# Mechaduino01.net
KiCad netlist of a schematic drawn in EAGLE
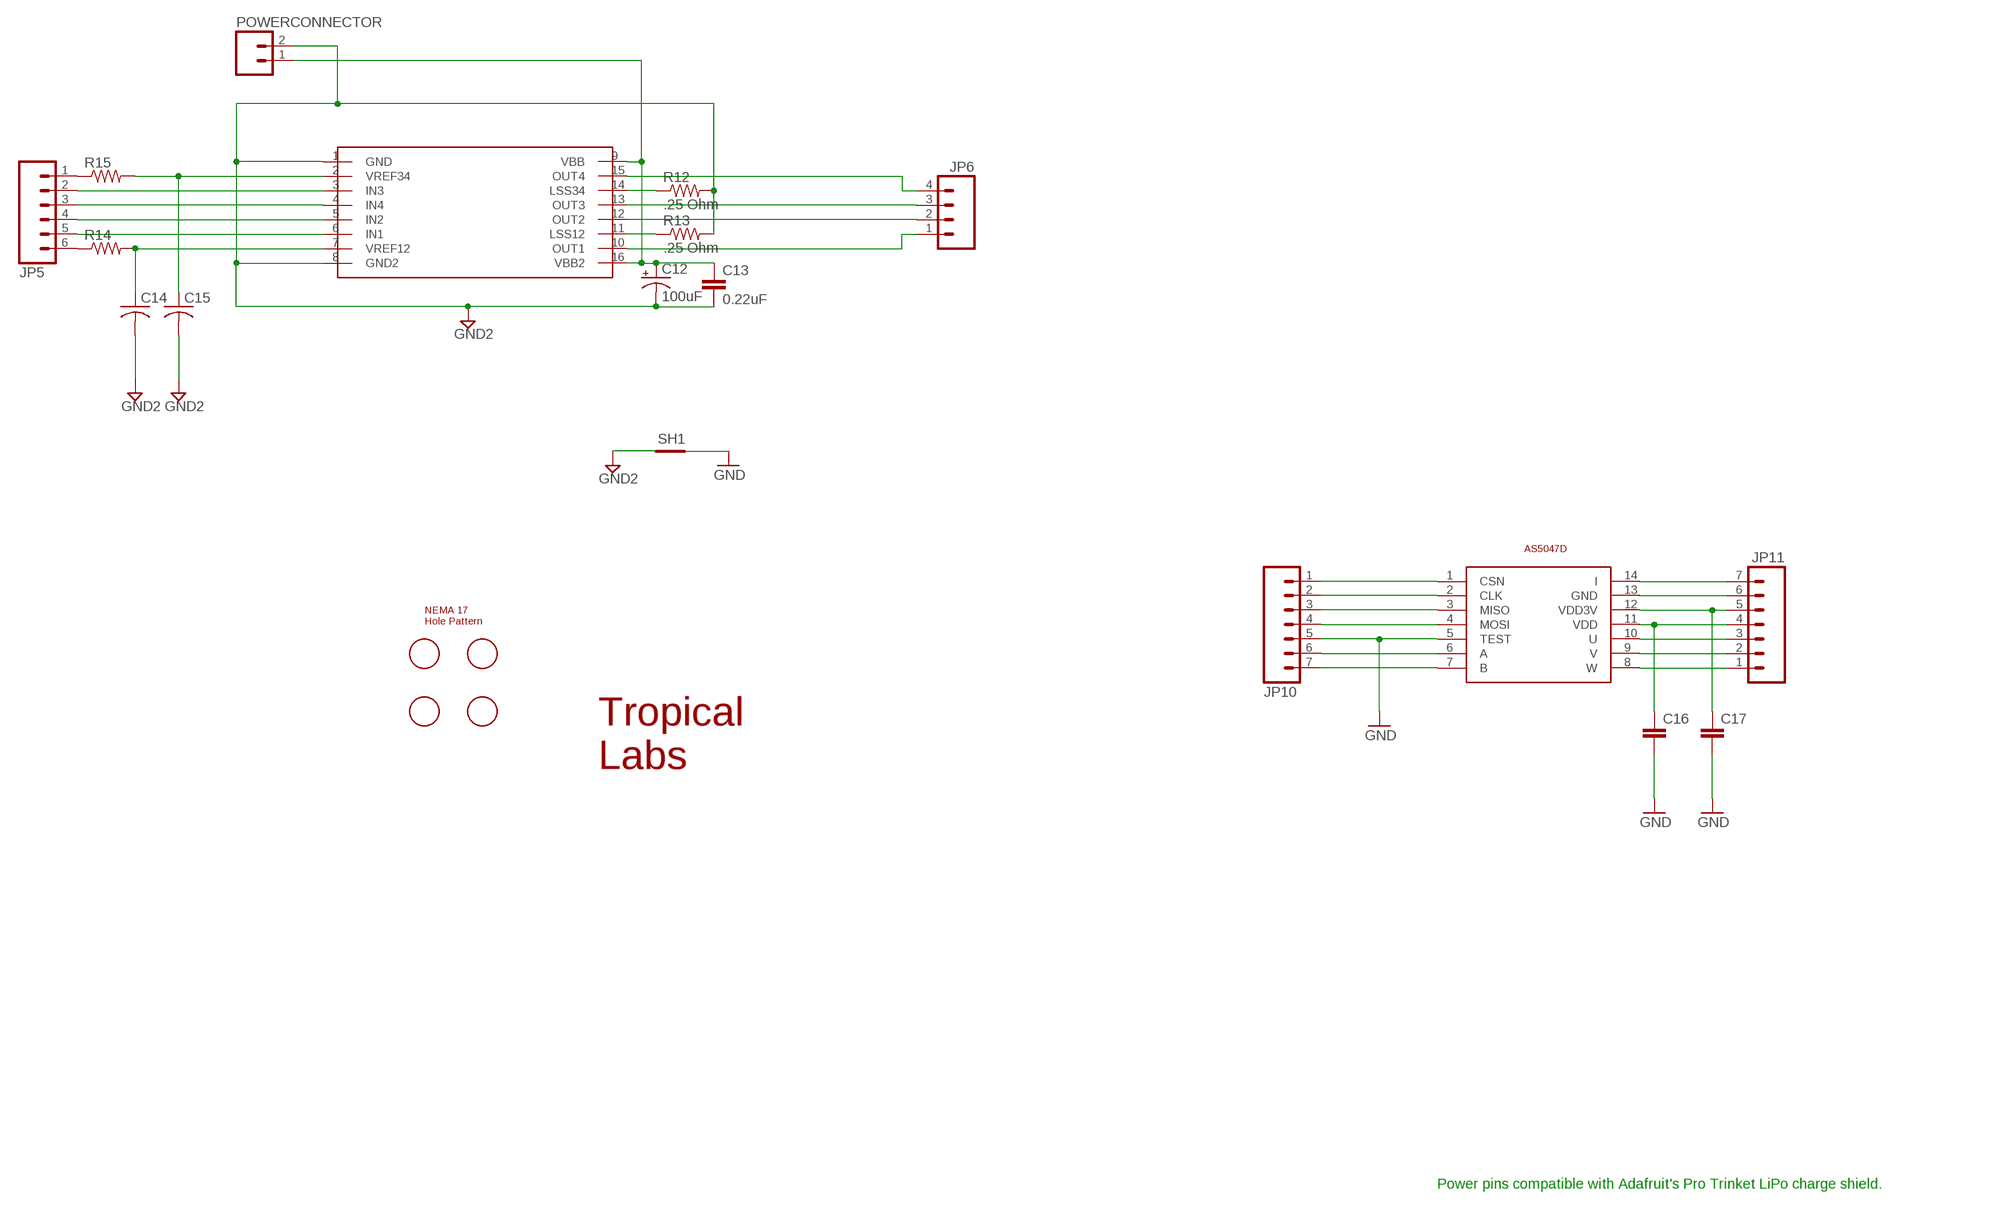
[diagram p0: schematic, sheet 1, part 1 of 2]
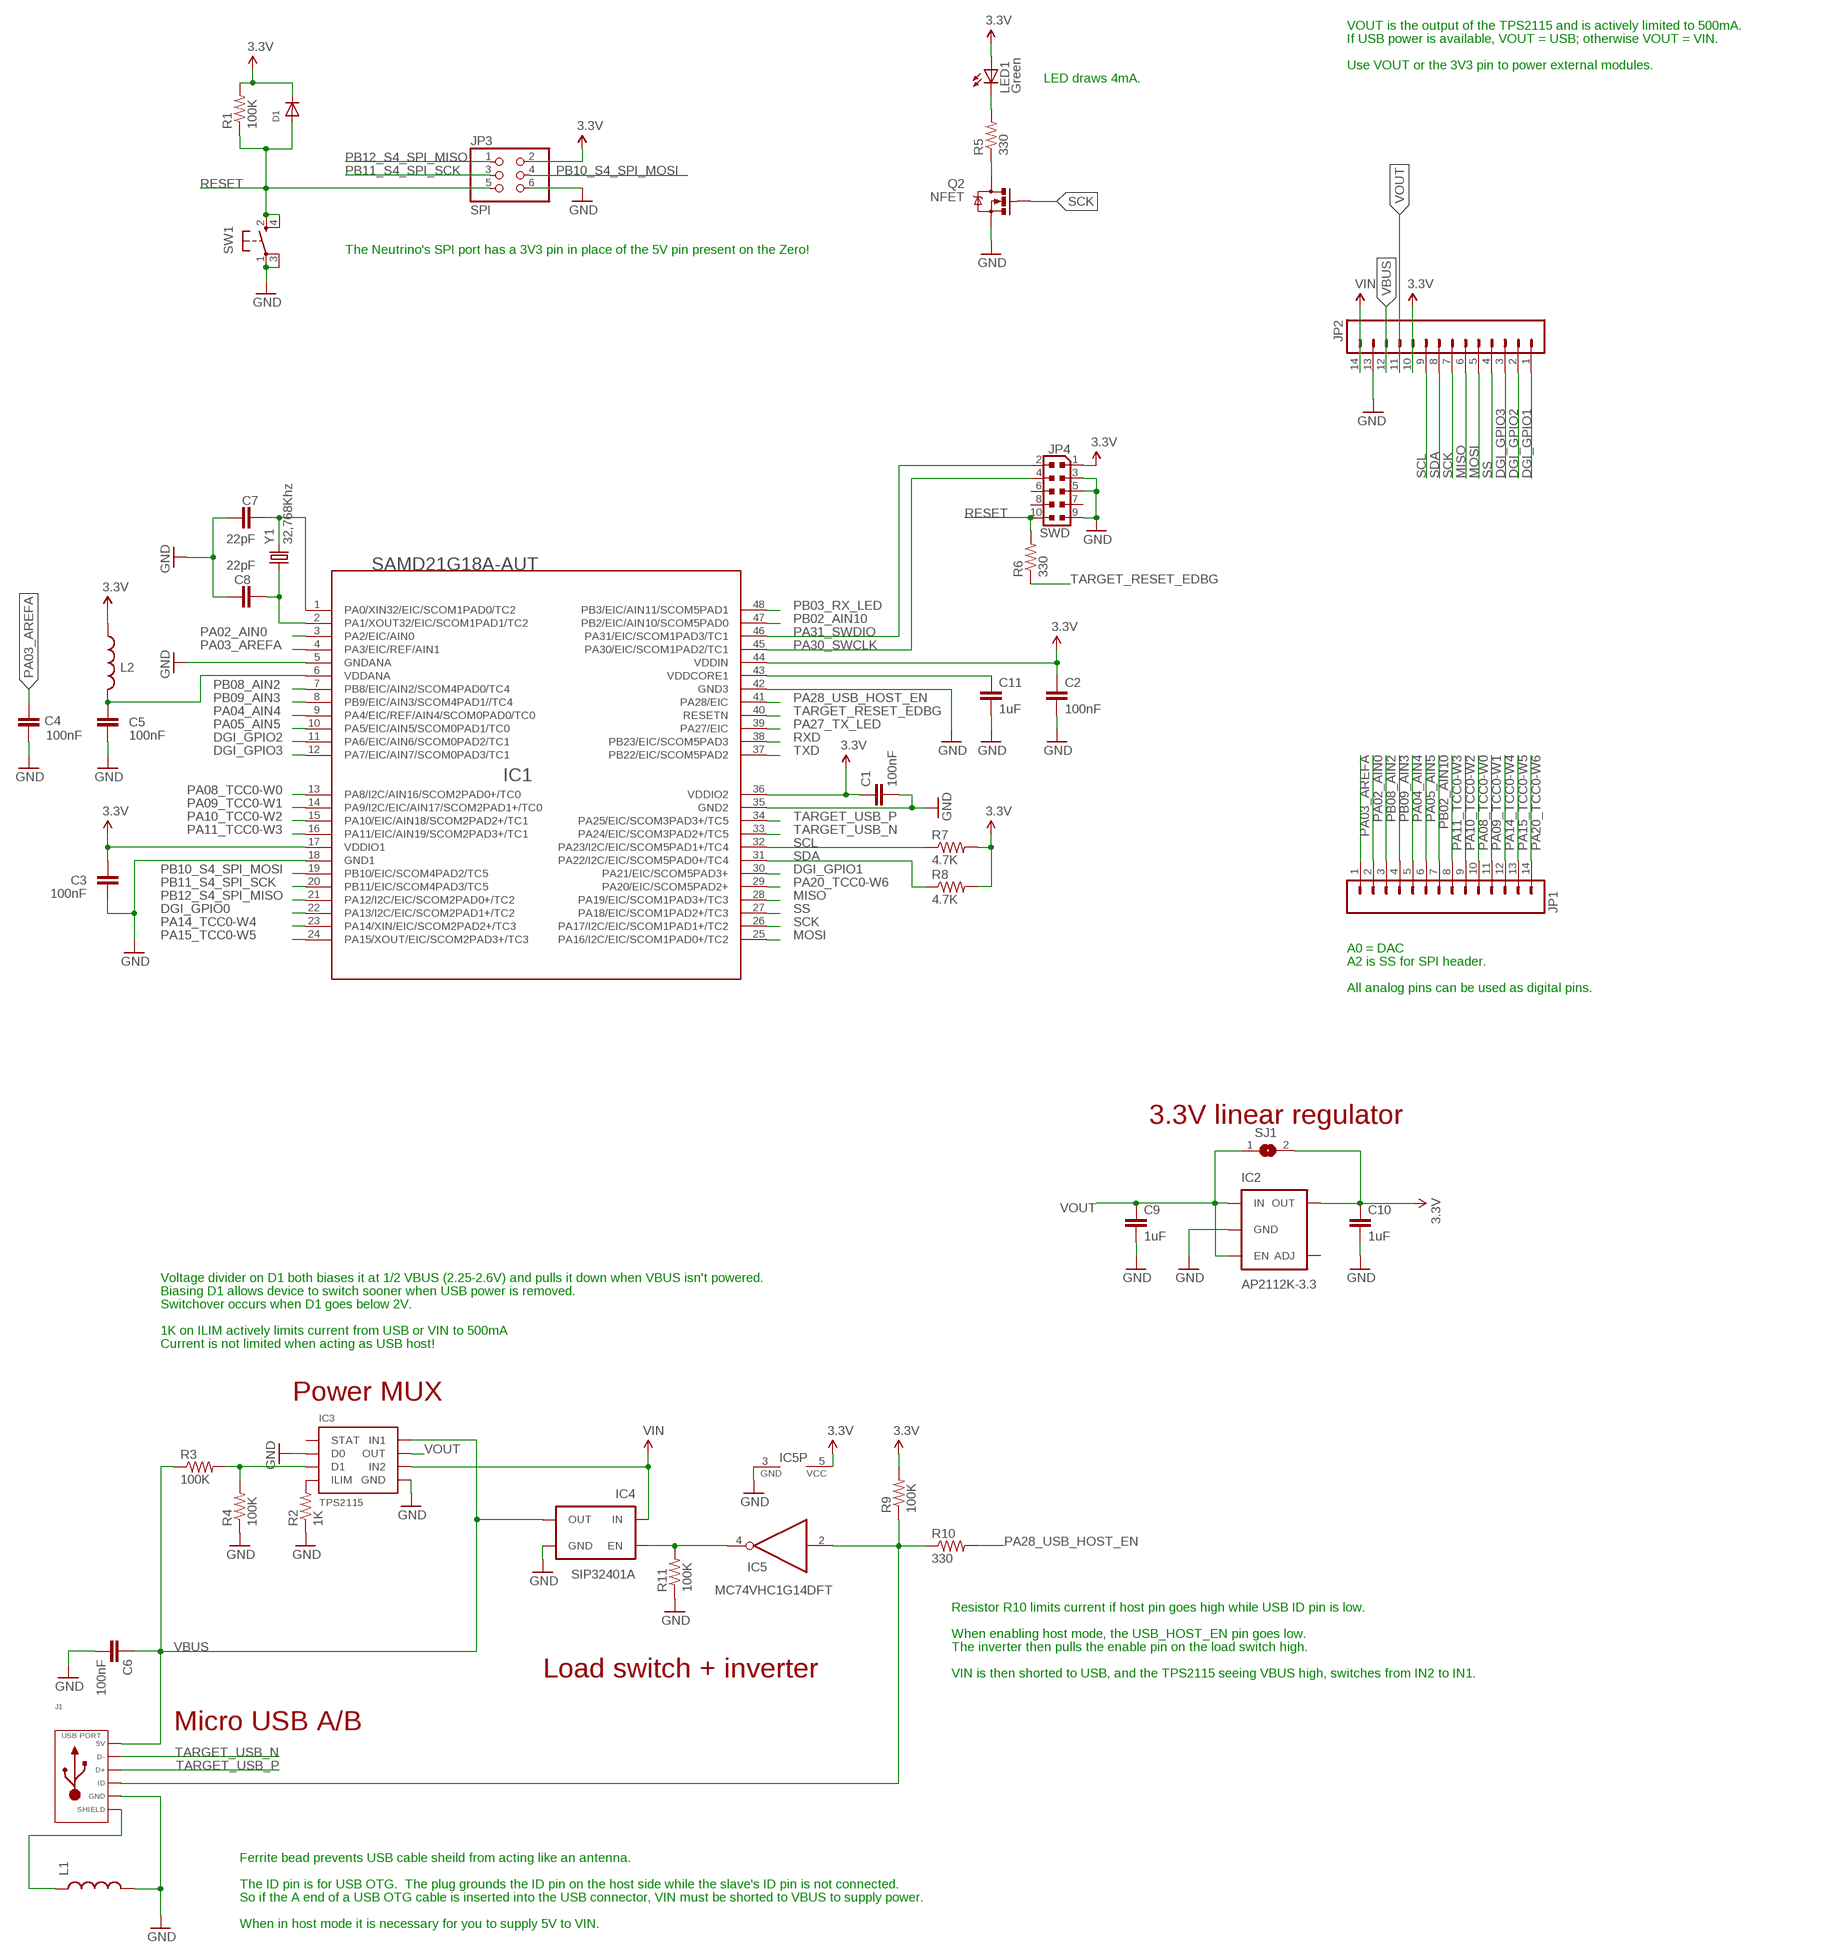
[diagram p1: schematic, sheet 1, part 2 of 2]

(export (version "E")
  (design (tool "Eeschema 10.0.6"))
  (components
    (comp (ref "C1")
      (value "100nF")
      (footprint "eagle-import:0402-CAP")
      (libsource (lib "eagle-import") (part "CAP0402"))
    )
    (comp (ref "C2")
      (value "100nF")
      (footprint "eagle-import:0402-CAP")
      (libsource (lib "eagle-import") (part "CAP0402"))
    )
    (comp (ref "C3")
      (value "100nF")
      (footprint "eagle-import:0402-CAP")
      (libsource (lib "eagle-import") (part "CAP0402"))
    )
    (comp (ref "C4")
      (value "100nF")
      (footprint "eagle-import:0402-CAP")
      (libsource (lib "eagle-import") (part "CAP0402"))
    )
    (comp (ref "C5")
      (value "100nF")
      (footprint "eagle-import:0402-CAP")
      (libsource (lib "eagle-import") (part "CAP0402"))
    )
    (comp (ref "C6")
      (value "100nF")
      (footprint "eagle-import:0402-CAP")
      (libsource (lib "eagle-import") (part "CAP0402"))
    )
    (comp (ref "C7")
      (value "22pF")
      (footprint "eagle-import:0402-CAP")
      (libsource (lib "eagle-import") (part "CAP0402"))
    )
    (comp (ref "C8")
      (value "22pF")
      (footprint "eagle-import:0402-CAP")
      (libsource (lib "eagle-import") (part "CAP0402"))
    )
    (comp (ref "C9")
      (value "1uF")
      (footprint "eagle-import:0402-CAP")
      (libsource (lib "eagle-import") (part "CAP0402"))
    )
    (comp (ref "C10")
      (value "1uF")
      (footprint "eagle-import:0402-CAP")
      (libsource (lib "eagle-import") (part "CAP0402"))
    )
    (comp (ref "C11")
      (value "1uF")
      (footprint "eagle-import:0402-CAP")
      (libsource (lib "eagle-import") (part "CAP0402"))
    )
    (comp (ref "C12")
      (value "100uF")
      (footprint "eagle-import:CPOL-RADIAL-100UF-25V")
      (libsource (lib "eagle-import") (part "CAP_POLPTH1"))
    )
    (comp (ref "C13")
      (value "0.22uF")
      (footprint "eagle-import:CAP-PTH-SMALLEZ")
      (libsource (lib "eagle-import") (part "CAPEZ"))
    )
    (comp (ref "C14")
      (value "C-US050-035X075")
      (footprint "eagle-import:C050-035X075")
      (libsource (lib "eagle-import") (part "C-US050-035X075"))
    )
    (comp (ref "C15")
      (value "C-US050-035X075")
      (footprint "eagle-import:C050-035X075")
      (libsource (lib "eagle-import") (part "C-US050-035X075"))
    )
    (comp (ref "C16")
      (value "CAP0402")
      (footprint "eagle-import:0402-CAP")
      (libsource (lib "eagle-import") (part "CAP0402"))
    )
    (comp (ref "C17")
      (value "CAP0402")
      (footprint "eagle-import:0402-CAP")
      (libsource (lib "eagle-import") (part "CAP0402"))
    )
    (comp (ref "D1")
      (value "DIODESOD-523")
      (footprint "eagle-import:SOD-523")
      (libsource (lib "eagle-import") (part "DIODESOD-523"))
    )
    (comp (ref "IC1")
      (value "SAMD21G18A-AUT")
      (footprint "eagle-import:INTEGRATEDCIRCUITS_TQFP48-7X7")
      (libsource (lib "eagle-import") (part "INTEGRATEDCIRCUITS_1792_SAMD21G18A-AUT"))
    )
    (comp (ref "IC2")
      (value "AP2112K-3.3")
      (footprint "eagle-import:SOT23-5")
      (libsource (lib "eagle-import") (part "AP2202-ADJ"))
    )
    (comp (ref "IC3")
      (value "TPS2115")
      (footprint "eagle-import:8-VDFN")
      (libsource (lib "eagle-import") (part "TPS2115"))
    )
    (comp (ref "IC4")
      (value "SIP32401A")
      (footprint "eagle-import:TDFN4")
      (libsource (lib "eagle-import") (part "SIP32401A"))
    )
    (comp (ref "IC5")
      (value "MC74VHC1G14DFT")
      (footprint "eagle-import:SC70-5")
      (libsource (lib "eagle-import") (part "741G04DCKAHC"))
    )
    (comp (ref "J1")
      (value "USB_MICRO_RIGHT")
      (footprint "eagle-import:MICROUSB-RIGHT")
      (libsource (lib "eagle-import") (part "USB_MICRO_RIGHT"))
    )
    (comp (ref "JP1")
      (value "M14NOSILK_SMALLPADS")
      (footprint "eagle-import:1X14_NO_SILK_SMALLPADS")
      (libsource (lib "eagle-import") (part "M14NOSILK_SMALLPADS"))
    )
    (comp (ref "JP2")
      (value "M14NOSILK_SMALLPADS")
      (footprint "eagle-import:1X14_NO_SILK_SMALLPADS")
      (libsource (lib "eagle-import") (part "M14NOSILK_SMALLPADS"))
    )
    (comp (ref "JP3")
      (value "SPI")
      (footprint "eagle-import:CONNETTORI_2X03")
      (fields (field (name "PART_NUMBER") "PH254-203DF118A00V"))
      (libsource (lib "eagle-import") (part "CONNETTORI_0114_PH254-203DF118A00V"))
    )
    (comp (ref "JP4")
      (value "SWD")
      (footprint "eagle-import:CONNETTORI_PINHEAD-2X5-P127")
      (libsource (lib "eagle-import") (part "CONNETTORI_0171_PH127-205DF055G00A"))
    )
    (comp (ref "JP5")
      (value "M06SILK_FEMALE_PTH")
      (footprint "eagle-import:1X06")
      (libsource (lib "eagle-import") (part "M06SILK_FEMALE_PTH"))
    )
    (comp (ref "JP6")
      (value "M04PTH")
      (footprint "eagle-import:1X04")
      (libsource (lib "eagle-import") (part "M04PTH"))
    )
    (comp (ref "JP10")
      (value "M07")
      (footprint "eagle-import:1X07")
      (libsource (lib "eagle-import") (part "M07"))
    )
    (comp (ref "JP11")
      (value "M07")
      (footprint "eagle-import:1X07")
      (libsource (lib "eagle-import") (part "M07"))
    )
    (comp (ref "L1")
      (value "INDUCTOR0603-TDK")
      (footprint "eagle-import:0603-TDK")
      (libsource (lib "eagle-import") (part "INDUCTOR0603-TDK"))
    )
    (comp (ref "L2")
      (value "INDUCTOR0603-TDK")
      (footprint "eagle-import:0603-TDK")
      (libsource (lib "eagle-import") (part "INDUCTOR0603-TDK"))
    )
    (comp (ref "LED1")
      (value "Green")
      (footprint "eagle-import:CHIPLED_0805")
      (fields (field (name "PART_NUMBER") "KPT-2012YC"))
      (libsource (lib "eagle-import") (part "0044_KPT-2012YC"))
    )
    (comp (ref "POWERCONNECTOR")
      (value "M025MM")
      (footprint "eagle-import:SCREWTERMINAL-5MM-2")
      (libsource (lib "eagle-import") (part "M025MM"))
    )
    (comp (ref "Q2")
      (value "NFET")
      (footprint "eagle-import:SOT323")
      (libsource (lib "eagle-import") (part "MOSFET-NCHANNEL2N7002PW"))
    )
    (comp (ref "R1")
      (value "100K")
      (footprint "eagle-import:R0402-VISHAY")
      (libsource (lib "eagle-import") (part "R-US_R0402-VISHAY"))
    )
    (comp (ref "R2")
      (value "1K")
      (footprint "eagle-import:R0402-VISHAY")
      (libsource (lib "eagle-import") (part "R-US_R0402-VISHAY"))
    )
    (comp (ref "R3")
      (value "100K")
      (footprint "eagle-import:R0402-VISHAY")
      (libsource (lib "eagle-import") (part "R-US_R0402-VISHAY"))
    )
    (comp (ref "R4")
      (value "100K")
      (footprint "eagle-import:R0402-VISHAY")
      (libsource (lib "eagle-import") (part "R-US_R0402-VISHAY"))
    )
    (comp (ref "R5")
      (value "330")
      (footprint "eagle-import:R0402-VISHAY")
      (libsource (lib "eagle-import") (part "R-US_R0402-VISHAY"))
    )
    (comp (ref "R6")
      (value "330")
      (footprint "eagle-import:R0402-VISHAY")
      (libsource (lib "eagle-import") (part "R-US_R0402-VISHAY"))
    )
    (comp (ref "R7")
      (value "4.7K")
      (footprint "eagle-import:R0402-VISHAY")
      (libsource (lib "eagle-import") (part "R-US_R0402-VISHAY"))
    )
    (comp (ref "R8")
      (value "4.7K")
      (footprint "eagle-import:R0402-VISHAY")
      (libsource (lib "eagle-import") (part "R-US_R0402-VISHAY"))
    )
    (comp (ref "R9")
      (value "100K")
      (footprint "eagle-import:R0402-VISHAY")
      (libsource (lib "eagle-import") (part "R-US_R0402-VISHAY"))
    )
    (comp (ref "R10")
      (value "330")
      (footprint "eagle-import:R0402-VISHAY")
      (libsource (lib "eagle-import") (part "R-US_R0402-VISHAY"))
    )
    (comp (ref "R11")
      (value "100K")
      (footprint "eagle-import:R0402-VISHAY")
      (libsource (lib "eagle-import") (part "R-US_R0402-VISHAY"))
    )
    (comp (ref "R12")
      (value ".25 Ohm")
      (footprint "eagle-import:0204V")
      (libsource (lib "eagle-import") (part "resistor_R-US_0204/2V"))
    )
    (comp (ref "R13")
      (value ".25 Ohm")
      (footprint "eagle-import:0204V")
      (libsource (lib "eagle-import") (part "resistor_R-US_0204/2V"))
    )
    (comp (ref "R14")
      (value "R-US_0204/2V")
      (footprint "eagle-import:0204V")
      (libsource (lib "eagle-import") (part "resistor_R-US_0204/2V"))
    )
    (comp (ref "R15")
      (value "R-US_0204/2V")
      (footprint "eagle-import:0204V")
      (libsource (lib "eagle-import") (part "resistor_R-US_0204/2V"))
    )
    (comp (ref "SH1")
      (value "SHORT-HA5")
      (footprint "eagle-import:SHORT_ALL-50")
      (libsource (lib "eagle-import") (part "SHORT-HA5"))
    )
    (comp (ref "SJ1") (value "SJ") (footprint "eagle-import:SJ") (libsource (lib "eagle-import") (part "SJ")))
    (comp (ref "SW1")
      (value "SPST_TACT-KMR2")
      (footprint "eagle-import:KMR2")
      (libsource (lib "eagle-import") (part "SPST_TACT-KMR2"))
    )
    (comp (ref "U$1")
      (value "AVAGO_DRIVER")
      (footprint "eagle-import:TSSOP16")
      (libsource (lib "eagle-import") (part "AVAGO_DRIVER"))
    )
    (comp (ref "U$2")
      (value "NEMA17_HOLE_PATTERN")
      (footprint "eagle-import:NEMA17_HOLE_PATTERN")
      (libsource (lib "eagle-import") (part "NEMA17_HOLE_PATTERN"))
    )
    (comp (ref "U$3")
      (value "TROPICAL_LABS_LOGO_1LOGO2")
      (footprint "eagle-import:LOGO2")
      (libsource (lib "eagle-import") (part "TROPICAL_LABS_LOGO_1LOGO2"))
    )
    (comp (ref "U$4")
      (value "AS5047D")
      (footprint "eagle-import:TSSOP14")
      (libsource (lib "eagle-import") (part "AS5047D"))
    )
    (comp (ref "Y1")
      (value "32,768Khz")
      (footprint "eagle-import:CRYSTAL-SMD-2.0X1.2")
      (libsource (lib "eagle-import") (part "CRYSTAL2012"))
    )
  )
  (nets
    (net (code "1") (name "/DGI_GPIO0") (class "Default")
      (node (ref "IC1") (pin "22") (pinfunction "PA13/I2C/EIC/SCOM2PAD1+/TC2_22") (pintype "bidirectional"))
    )
    (net (code "2") (name "/DGI_GPIO1") (class "Default")
      (node (ref "IC1") (pin "30") (pinfunction "PA21/EIC/SCOM5PAD3+_30") (pintype "bidirectional"))
      (node (ref "JP2") (pin "1") (pinfunction "1_1") (pintype "passive"))
    )
    (net (code "3") (name "/DGI_GPIO2") (class "Default")
      (node (ref "IC1") (pin "11") (pinfunction "PA6/EIC/AIN6/SCOM0PAD2/TC1_11") (pintype "bidirectional"))
      (node (ref "JP2") (pin "2") (pinfunction "2_2") (pintype "passive"))
    )
    (net (code "4") (name "/DGI_GPIO3") (class "Default")
      (node (ref "IC1") (pin "12") (pinfunction "PA7/EIC/AIN7/SCOM0PAD3/TC1_12") (pintype "bidirectional"))
      (node (ref "JP2") (pin "3") (pinfunction "3_3") (pintype "passive"))
    )
    (net (code "5") (name "/MISO") (class "Default")
      (node (ref "IC1") (pin "28") (pinfunction "PA19/EIC/SCOM1PAD3+/TC3_28") (pintype "bidirectional"))
      (node (ref "JP2") (pin "6") (pinfunction "6_6") (pintype "passive"))
    )
    (net (code "6") (name "/MOSI") (class "Default")
      (node (ref "IC1") (pin "25") (pinfunction "PA16/I2C/EIC/SCOM1PAD0+/TC2_25") (pintype "bidirectional"))
      (node (ref "JP2") (pin "5") (pinfunction "5_5") (pintype "passive"))
    )
    (net (code "7") (name "/PA02_AIN0") (class "Default")
      (node (ref "IC1") (pin "3") (pinfunction "PA2/EIC/AIN0_3") (pintype "bidirectional"))
      (node (ref "JP1") (pin "2") (pinfunction "2_2") (pintype "passive"))
    )
    (net (code "8") (name "/PA04_AIN4") (class "Default")
      (node (ref "IC1") (pin "9") (pinfunction "PA4/EIC/REF/AIN4/SCOM0PAD0/TC0_9") (pintype "bidirectional"))
      (node (ref "JP1") (pin "5") (pinfunction "5_5") (pintype "passive"))
    )
    (net (code "9") (name "/PA05_AIN5") (class "Default")
      (node (ref "IC1") (pin "10") (pinfunction "PA5/EIC/AIN5/SCOM0PAD1/TC0_10") (pintype "bidirectional"))
      (node (ref "JP1") (pin "6") (pinfunction "6_6") (pintype "passive"))
    )
    (net (code "10") (name "/PA08_TCC0-W0") (class "Default")
      (node (ref "IC1") (pin "13") (pinfunction "PA8/I2C/AIN16/SCOM2PAD0+/TC0_13") (pintype "bidirectional"))
      (node (ref "JP1") (pin "10") (pinfunction "10_10") (pintype "passive"))
    )
    (net (code "11") (name "/PA09_TCC0-W1") (class "Default")
      (node (ref "IC1") (pin "14") (pinfunction "PA9/I2C/EIC/AIN17/SCOM2PAD1+/TC0_14") (pintype "bidirectional"))
      (node (ref "JP1") (pin "11") (pinfunction "11_11") (pintype "passive"))
    )
    (net (code "12") (name "/PA10_TCC0-W2") (class "Default")
      (node (ref "IC1") (pin "15") (pinfunction "PA10/EIC/AIN18/SCOM2PAD2+/TC1_15") (pintype "bidirectional"))
      (node (ref "JP1") (pin "9") (pinfunction "9_9") (pintype "passive"))
    )
    (net (code "13") (name "/PA11_TCC0-W3") (class "Default")
      (node (ref "IC1") (pin "16") (pinfunction "PA11/EIC/AIN19/SCOM2PAD3+/TC1_16") (pintype "bidirectional"))
      (node (ref "JP1") (pin "8") (pinfunction "8_8") (pintype "passive"))
    )
    (net (code "14") (name "/PA14_TCC0-W4") (class "Default")
      (node (ref "IC1") (pin "23") (pinfunction "PA14/XIN/EIC/SCOM2PAD2+/TC3_23") (pintype "bidirectional"))
      (node (ref "JP1") (pin "12") (pinfunction "12_12") (pintype "passive"))
    )
    (net (code "15") (name "/PA15_TCC0-W5") (class "Default")
      (node (ref "IC1") (pin "24") (pinfunction "PA15/XOUT/EIC/SCOM2PAD3+/TC3_24") (pintype "bidirectional"))
      (node (ref "JP1") (pin "13") (pinfunction "13_13") (pintype "passive"))
    )
    (net (code "16") (name "/PA20_TCC0-W6") (class "Default")
      (node (ref "IC1") (pin "29") (pinfunction "PA20/EIC/SCOM5PAD2+_29") (pintype "bidirectional"))
      (node (ref "JP1") (pin "14") (pinfunction "14_14") (pintype "passive"))
    )
    (net (code "17") (name "/PA27_TX_LED") (class "Default")
      (node (ref "IC1") (pin "39") (pinfunction "PA27/EIC_39") (pintype "bidirectional"))
    )
    (net (code "18") (name "/PA28_USB_HOST_EN") (class "Default")
      (node (ref "IC1") (pin "41") (pinfunction "PA28/EIC_41") (pintype "bidirectional"))
      (node (ref "R10") (pin "2") (pinfunction "2_2") (pintype "passive"))
    )
    (net (code "19") (name "/PA30_SWCLK") (class "Default")
      (node (ref "IC1") (pin "45") (pinfunction "PA30/EIC/SCOM1PAD2/TC1_45") (pintype "bidirectional"))
      (node (ref "JP4") (pin "4") (pinfunction "4_4") (pintype "passive"))
    )
    (net (code "20") (name "/PA31_SWDIO") (class "Default")
      (node (ref "IC1") (pin "46") (pinfunction "PA31/EIC/SCOM1PAD3/TC1_46") (pintype "bidirectional"))
      (node (ref "JP4") (pin "2") (pinfunction "2_2") (pintype "passive"))
    )
    (net (code "21") (name "/PB02_AIN10") (class "Default")
      (node (ref "IC1") (pin "47") (pinfunction "PB2/EIC/AIN10/SCOM5PAD0_47") (pintype "bidirectional"))
      (node (ref "JP1") (pin "7") (pinfunction "7_7") (pintype "passive"))
    )
    (net (code "22") (name "/PB03_RX_LED") (class "Default")
      (node (ref "IC1") (pin "48") (pinfunction "PB3/EIC/AIN11/SCOM5PAD1_48") (pintype "bidirectional"))
    )
    (net (code "23") (name "/PB08_AIN2") (class "Default")
      (node (ref "IC1") (pin "7") (pinfunction "PB8/EIC/AIN2/SCOM4PAD0/TC4_7") (pintype "bidirectional"))
      (node (ref "JP1") (pin "3") (pinfunction "3_3") (pintype "passive"))
    )
    (net (code "24") (name "/PB09_AIN3") (class "Default")
      (node (ref "IC1") (pin "8") (pinfunction "PB9/EIC/AIN3/SCOM4PAD1//TC4_8") (pintype "bidirectional"))
      (node (ref "JP1") (pin "4") (pinfunction "4_4") (pintype "passive"))
    )
    (net (code "25") (name "/PB10_S4_SPI_MOSI") (class "Default")
      (node (ref "IC1") (pin "19") (pinfunction "PB10/EIC/SCOM4PAD2/TC5_19") (pintype "bidirectional"))
      (node (ref "JP3") (pin "4") (pinfunction "4_4") (pintype "passive"))
    )
    (net (code "26") (name "/PB11_S4_SPI_SCK") (class "Default")
      (node (ref "IC1") (pin "20") (pinfunction "PB11/EIC/SCOM4PAD3/TC5_20") (pintype "bidirectional"))
      (node (ref "JP3") (pin "3") (pinfunction "3_3") (pintype "passive"))
    )
    (net (code "27") (name "/PB12_S4_SPI_MISO") (class "Default")
      (node (ref "IC1") (pin "21") (pinfunction "PA12/I2C/EIC/SCOM2PAD0+/TC2_21") (pintype "bidirectional"))
      (node (ref "JP3") (pin "1") (pinfunction "1_1") (pintype "passive"))
    )
    (net (code "28") (name "/RESET") (class "Default")
      (node (ref "D1") (pin "A") (pinfunction "A_A") (pintype "passive"))
      (node (ref "JP3") (pin "5") (pinfunction "5_5") (pintype "passive"))
      (node (ref "JP4") (pin "10") (pinfunction "10_10") (pintype "passive"))
      (node (ref "R1") (pin "1") (pinfunction "1_1") (pintype "passive"))
      (node (ref "R6") (pin "2") (pinfunction "2_2") (pintype "passive"))
      (node (ref "SW1") (pin "2") (pinfunction "S_2") (pintype "passive"))
      (node (ref "SW1") (pin "4") (pinfunction "S1_4") (pintype "passive"))
    )
    (net (code "29") (name "/RXD") (class "Default")
      (node (ref "IC1") (pin "38") (pinfunction "PB23/EIC/SCOM5PAD3_38") (pintype "bidirectional"))
    )
    (net (code "30") (name "/SCL") (class "Default")
      (node (ref "IC1") (pin "32") (pinfunction "PA23/I2C/EIC/SCOM5PAD1+/TC4_32") (pintype "bidirectional"))
      (node (ref "JP2") (pin "9") (pinfunction "9_9") (pintype "passive"))
      (node (ref "R7") (pin "1") (pinfunction "1_1") (pintype "passive"))
    )
    (net (code "31") (name "/SDA") (class "Default")
      (node (ref "IC1") (pin "31") (pinfunction "PA22/I2C/EIC/SCOM5PAD0+/TC4_31") (pintype "bidirectional"))
      (node (ref "JP2") (pin "8") (pinfunction "8_8") (pintype "passive"))
      (node (ref "R8") (pin "1") (pinfunction "1_1") (pintype "passive"))
    )
    (net (code "32") (name "/SS") (class "Default")
      (node (ref "IC1") (pin "27") (pinfunction "PA18/EIC/SCOM1PAD2+/TC3_27") (pintype "bidirectional"))
      (node (ref "JP2") (pin "4") (pinfunction "4_4") (pintype "passive"))
    )
    (net (code "33") (name "/TARGET_RESET_EDBG") (class "Default")
      (node (ref "IC1") (pin "40") (pinfunction "RESETN_40") (pintype "bidirectional"))
      (node (ref "R6") (pin "1") (pinfunction "1_1") (pintype "passive"))
    )
    (net (code "34") (name "/TARGET_USB_N") (class "Default")
      (node (ref "IC1") (pin "33") (pinfunction "PA24/EIC/SCOM3PAD2+/TC5_33") (pintype "bidirectional"))
      (node (ref "J1") (pin "2") (pinfunction "D-_2") (pintype "bidirectional"))
    )
    (net (code "35") (name "/TARGET_USB_P") (class "Default")
      (node (ref "IC1") (pin "34") (pinfunction "PA25/EIC/SCOM3PAD3+/TC5_34") (pintype "bidirectional"))
      (node (ref "J1") (pin "3") (pinfunction "D+_3") (pintype "bidirectional"))
    )
    (net (code "36") (name "/TXD") (class "Default")
      (node (ref "IC1") (pin "37") (pinfunction "PB22/EIC/SCOM5PAD2_37") (pintype "bidirectional"))
    )
    (net (code "37") (name "3.3V") (class "Default")
      (node (ref "C1") (pin "1") (pinfunction "1_1") (pintype "passive"))
      (node (ref "C10") (pin "1") (pinfunction "1_1") (pintype "passive"))
      (node (ref "C2") (pin "1") (pinfunction "1_1") (pintype "passive"))
      (node (ref "C3") (pin "2") (pinfunction "2_2") (pintype "passive"))
      (node (ref "D1") (pin "K") (pinfunction "C_K") (pintype "passive"))
      (node (ref "IC1") (pin "17") (pinfunction "VDDIO1_17") (pintype "power_in"))
      (node (ref "IC1") (pin "36") (pinfunction "VDDIO2_36") (pintype "power_in"))
      (node (ref "IC1") (pin "44") (pinfunction "VDDIN_44") (pintype "power_in"))
      (node (ref "IC2") (pin "5") (pinfunction "OUT_5") (pintype "passive"))
      (node (ref "IC5") (pin "5") (pinfunction "VCC_5") (pintype "power_in"))
      (node (ref "JP2") (pin "10") (pinfunction "10_10") (pintype "passive"))
      (node (ref "JP3") (pin "2") (pinfunction "2_2") (pintype "passive"))
      (node (ref "JP4") (pin "1") (pinfunction "1_1") (pintype "passive"))
      (node (ref "L2") (pin "1") (pinfunction "1_1") (pintype "passive"))
      (node (ref "LED1") (pin "A") (pinfunction "A_A") (pintype "passive"))
      (node (ref "R1") (pin "2") (pinfunction "2_2") (pintype "passive"))
      (node (ref "R7") (pin "2") (pinfunction "2_2") (pintype "passive"))
      (node (ref "R8") (pin "2") (pinfunction "2_2") (pintype "passive"))
      (node (ref "R9") (pin "2") (pinfunction "2_2") (pintype "passive"))
      (node (ref "SJ1") (pin "2") (pinfunction "2_2") (pintype "passive"))
    )
    (net (code "38") (name "GND") (class "Default")
      (node (ref "C1") (pin "2") (pinfunction "2_2") (pintype "passive"))
      (node (ref "C10") (pin "2") (pinfunction "2_2") (pintype "passive"))
      (node (ref "C11") (pin "2") (pinfunction "2_2") (pintype "passive"))
      (node (ref "C16") (pin "2") (pinfunction "2_2") (pintype "passive"))
      (node (ref "C17") (pin "2") (pinfunction "2_2") (pintype "passive"))
      (node (ref "C2") (pin "2") (pinfunction "2_2") (pintype "passive"))
      (node (ref "C3") (pin "1") (pinfunction "1_1") (pintype "passive"))
      (node (ref "C4") (pin "2") (pinfunction "2_2") (pintype "passive"))
      (node (ref "C5") (pin "2") (pinfunction "2_2") (pintype "passive"))
      (node (ref "C6") (pin "2") (pinfunction "2_2") (pintype "passive"))
      (node (ref "C7") (pin "1") (pinfunction "1_1") (pintype "passive"))
      (node (ref "C8") (pin "1") (pinfunction "1_1") (pintype "passive"))
      (node (ref "C9") (pin "2") (pinfunction "2_2") (pintype "passive"))
      (node (ref "IC1") (pin "18") (pinfunction "GND1_18") (pintype "power_in"))
      (node (ref "IC1") (pin "35") (pinfunction "GND2_35") (pintype "power_in"))
      (node (ref "IC1") (pin "42") (pinfunction "GND3_42") (pintype "power_in"))
      (node (ref "IC1") (pin "5") (pinfunction "GNDANA_5") (pintype "power_in"))
      (node (ref "IC2") (pin "2") (pinfunction "GND_2") (pintype "input"))
      (node (ref "IC3") (pin "2") (pinfunction "D0_2") (pintype "bidirectional"))
      (node (ref "IC3") (pin "5") (pinfunction "GND_5") (pintype "bidirectional"))
      (node (ref "IC3") (pin "P0") (pinfunction "GND_P0") (pintype "bidirectional"))
      (node (ref "IC3") (pin "V0") (pinfunction "GND_V0") (pintype "bidirectional"))
      (node (ref "IC3") (pin "V1") (pinfunction "GND_V1") (pintype "bidirectional"))
      (node (ref "IC3") (pin "V2") (pinfunction "GND_V2") (pintype "bidirectional"))
      (node (ref "IC3") (pin "V3") (pinfunction "GND_V3") (pintype "bidirectional"))
      (node (ref "IC3") (pin "V4") (pinfunction "GND_V4") (pintype "bidirectional"))
      (node (ref "IC4") (pin "0") (pinfunction "GND_0") (pintype "power_in"))
      (node (ref "IC4") (pin "2") (pinfunction "GND_2") (pintype "power_in"))
      (node (ref "IC5") (pin "3") (pinfunction "GND_3") (pintype "power_in"))
      (node (ref "J1") (pin "5") (pinfunction "GND_5") (pintype "power_in"))
      (node (ref "JP10") (pin "5") (pinfunction "5_5") (pintype "passive"))
      (node (ref "JP2") (pin "13") (pinfunction "13_13") (pintype "passive"))
      (node (ref "JP3") (pin "6") (pinfunction "6_6") (pintype "passive"))
      (node (ref "JP4") (pin "3") (pinfunction "3_3") (pintype "passive"))
      (node (ref "JP4") (pin "5") (pinfunction "5_5") (pintype "passive"))
      (node (ref "JP4") (pin "9") (pinfunction "9_9") (pintype "passive"))
      (node (ref "L1") (pin "2") (pinfunction "2_2") (pintype "passive"))
      (node (ref "Q2") (pin "2") (pinfunction "S_2") (pintype "passive"))
      (node (ref "R11") (pin "1") (pinfunction "1_1") (pintype "passive"))
      (node (ref "R2") (pin "1") (pinfunction "1_1") (pintype "passive"))
      (node (ref "R4") (pin "1") (pinfunction "1_1") (pintype "passive"))
      (node (ref "SH1") (pin "2") (pinfunction "P$2_2") (pintype "bidirectional"))
      (node (ref "SW1") (pin "1") (pinfunction "P_1") (pintype "passive"))
      (node (ref "SW1") (pin "3") (pinfunction "P1_3") (pintype "passive"))
      (node (ref "U$4") (pin "5") (pinfunction "TEST_5") (pintype "bidirectional"))
    )
    (net (code "39") (name "GND2") (class "Default")
      (node (ref "C12") (pin "2") (pinfunction "-_2") (pintype "passive"))
      (node (ref "C13") (pin "2") (pinfunction "2_2") (pintype "passive"))
      (node (ref "C14") (pin "2") (pinfunction "2_2") (pintype "passive"))
      (node (ref "C15") (pin "2") (pinfunction "2_2") (pintype "passive"))
      (node (ref "POWERCONNECTOR") (pin "2") (pinfunction "2_2") (pintype "passive"))
      (node (ref "R12") (pin "2") (pinfunction "2_2") (pintype "passive"))
      (node (ref "R13") (pin "2") (pinfunction "2_2") (pintype "passive"))
      (node (ref "SH1") (pin "1") (pinfunction "P$1_1") (pintype "bidirectional"))
      (node (ref "U$1") (pin "1") (pinfunction "GND_1") (pintype "bidirectional"))
      (node (ref "U$1") (pin "8") (pinfunction "GND2_8") (pintype "bidirectional"))
    )
    (net (code "40") (name "Net-(C12-+)") (class "Default")
      (node (ref "C12") (pin "1") (pinfunction "+_1") (pintype "passive"))
      (node (ref "C13") (pin "1") (pinfunction "1_1") (pintype "passive"))
      (node (ref "POWERCONNECTOR") (pin "1") (pinfunction "1_1") (pintype "passive"))
      (node (ref "U$1") (pin "16") (pinfunction "VBB2_16") (pintype "bidirectional"))
      (node (ref "U$1") (pin "9") (pinfunction "VBB_9") (pintype "bidirectional"))
    )
    (net (code "41") (name "Net-(IC1-PA0{slash}XIN32{slash}EIC{slash}SCOM1PAD0{slash}TC2)") (class "Default")
      (node (ref "C7") (pin "2") (pinfunction "2_2") (pintype "passive"))
      (node (ref "IC1") (pin "1") (pinfunction "PA0/XIN32/EIC/SCOM1PAD0/TC2_1") (pintype "bidirectional"))
      (node (ref "Y1") (pin "2") (pinfunction "2_2") (pintype "passive"))
    )
    (net (code "42") (name "Net-(IC1-PA1{slash}XOUT32{slash}EIC{slash}SCOM1PAD1{slash}TC2)") (class "Default")
      (node (ref "C8") (pin "2") (pinfunction "2_2") (pintype "passive"))
      (node (ref "IC1") (pin "2") (pinfunction "PA1/XOUT32/EIC/SCOM1PAD1/TC2_2") (pintype "bidirectional"))
      (node (ref "Y1") (pin "1") (pinfunction "1_1") (pintype "passive"))
    )
    (net (code "43") (name "Net-(IC1-VDDANA)") (class "Default")
      (node (ref "C5") (pin "1") (pinfunction "1_1") (pintype "passive"))
      (node (ref "IC1") (pin "6") (pinfunction "VDDANA_6") (pintype "power_in"))
      (node (ref "L2") (pin "2") (pinfunction "2_2") (pintype "passive"))
    )
    (net (code "44") (name "Net-(IC1-VDDCORE1)") (class "Default")
      (node (ref "C11") (pin "1") (pinfunction "1_1") (pintype "passive"))
      (node (ref "IC1") (pin "43") (pinfunction "VDDCORE1_43") (pintype "input"))
    )
    (net (code "45") (name "Net-(IC3-D1)") (class "Default")
      (node (ref "IC3") (pin "3") (pinfunction "D1_3") (pintype "bidirectional"))
      (node (ref "R3") (pin "2") (pinfunction "2_2") (pintype "passive"))
      (node (ref "R4") (pin "2") (pinfunction "2_2") (pintype "passive"))
    )
    (net (code "46") (name "Net-(IC3-ILIM)") (class "Default")
      (node (ref "IC3") (pin "4") (pinfunction "ILIM_4") (pintype "bidirectional"))
      (node (ref "R2") (pin "2") (pinfunction "2_2") (pintype "passive"))
    )
    (net (code "47") (name "Net-(IC4-EN)") (class "Default")
      (node (ref "IC4") (pin "4") (pinfunction "EN_4") (pintype "input"))
      (node (ref "IC5") (pin "4") (pinfunction "O_4") (pintype "output"))
      (node (ref "R11") (pin "2") (pinfunction "2_2") (pintype "passive"))
    )
    (net (code "48") (name "Net-(IC5A-I)") (class "Default")
      (node (ref "IC5") (pin "2") (pinfunction "I_2") (pintype "input"))
      (node (ref "J1") (pin "4") (pinfunction "ID_4") (pintype "bidirectional"))
      (node (ref "R10") (pin "1") (pinfunction "1_1") (pintype "passive"))
      (node (ref "R9") (pin "1") (pinfunction "1_1") (pintype "passive"))
    )
    (net (code "49") (name "Net-(J1-SLD-PadS1)") (class "Default")
      (node (ref "J1") (pin "S1") (pinfunction "SLD_S1") (pintype "power_in"))
      (node (ref "J1") (pin "S2") (pinfunction "SLD_S2") (pintype "power_in"))
      (node (ref "J1") (pin "S3") (pinfunction "SLD_S3") (pintype "power_in"))
      (node (ref "J1") (pin "S4") (pinfunction "SLD_S4") (pintype "power_in"))
      (node (ref "J1") (pin "S5") (pinfunction "SLD_S5") (pintype "power_in"))
      (node (ref "J1") (pin "S6") (pinfunction "SLD_S6") (pintype "power_in"))
      (node (ref "J1") (pin "S7") (pinfunction "SLD_S7") (pintype "power_in"))
      (node (ref "J1") (pin "S8") (pinfunction "SLD_S8") (pintype "power_in"))
      (node (ref "L1") (pin "1") (pinfunction "1_1") (pintype "passive"))
    )
    (net (code "50") (name "Net-(JP5-Pad1)") (class "Default")
      (node (ref "JP5") (pin "1") (pinfunction "1_1") (pintype "passive"))
      (node (ref "R15") (pin "1") (pinfunction "1_1") (pintype "passive"))
    )
    (net (code "51") (name "Net-(JP5-Pad6)") (class "Default")
      (node (ref "JP5") (pin "6") (pinfunction "6_6") (pintype "passive"))
      (node (ref "R14") (pin "1") (pinfunction "1_1") (pintype "passive"))
    )
    (net (code "52") (name "Net-(LED1-PadC)") (class "Default")
      (node (ref "LED1") (pin "C") (pinfunction "C_C") (pintype "passive"))
      (node (ref "R5") (pin "2") (pinfunction "2_2") (pintype "passive"))
    )
    (net (code "53") (name "Net-(Q2-D)") (class "Default")
      (node (ref "Q2") (pin "3") (pinfunction "D_3") (pintype "passive"))
      (node (ref "R5") (pin "1") (pinfunction "1_1") (pintype "passive"))
    )
    (net (code "54") (name "Net-(U$1-IN1)") (class "Default")
      (node (ref "JP5") (pin "5") (pinfunction "5_5") (pintype "passive"))
      (node (ref "U$1") (pin "6") (pinfunction "IN1_6") (pintype "bidirectional"))
    )
    (net (code "55") (name "Net-(U$1-IN2)") (class "Default")
      (node (ref "JP5") (pin "4") (pinfunction "4_4") (pintype "passive"))
      (node (ref "U$1") (pin "5") (pinfunction "IN2_5") (pintype "bidirectional"))
    )
    (net (code "56") (name "Net-(U$1-IN3)") (class "Default")
      (node (ref "JP5") (pin "2") (pinfunction "2_2") (pintype "passive"))
      (node (ref "U$1") (pin "3") (pinfunction "IN3_3") (pintype "bidirectional"))
    )
    (net (code "57") (name "Net-(U$1-IN4)") (class "Default")
      (node (ref "JP5") (pin "3") (pinfunction "3_3") (pintype "passive"))
      (node (ref "U$1") (pin "4") (pinfunction "IN4_4") (pintype "bidirectional"))
    )
    (net (code "58") (name "Net-(U$1-LSS12)") (class "Default")
      (node (ref "R13") (pin "1") (pinfunction "1_1") (pintype "passive"))
      (node (ref "U$1") (pin "11") (pinfunction "LSS12_11") (pintype "bidirectional"))
    )
    (net (code "59") (name "Net-(U$1-LSS34)") (class "Default")
      (node (ref "R12") (pin "1") (pinfunction "1_1") (pintype "passive"))
      (node (ref "U$1") (pin "14") (pinfunction "LSS34_14") (pintype "bidirectional"))
    )
    (net (code "60") (name "Net-(U$1-OUT1)") (class "Default")
      (node (ref "JP6") (pin "1") (pinfunction "1_1") (pintype "passive"))
      (node (ref "U$1") (pin "10") (pinfunction "OUT1_10") (pintype "bidirectional"))
    )
    (net (code "61") (name "Net-(U$1-OUT2)") (class "Default")
      (node (ref "JP6") (pin "2") (pinfunction "2_2") (pintype "passive"))
      (node (ref "U$1") (pin "12") (pinfunction "OUT2_12") (pintype "bidirectional"))
    )
    (net (code "62") (name "Net-(U$1-OUT3)") (class "Default")
      (node (ref "JP6") (pin "3") (pinfunction "3_3") (pintype "passive"))
      (node (ref "U$1") (pin "13") (pinfunction "OUT3_13") (pintype "bidirectional"))
    )
    (net (code "63") (name "Net-(U$1-OUT4)") (class "Default")
      (node (ref "JP6") (pin "4") (pinfunction "4_4") (pintype "passive"))
      (node (ref "U$1") (pin "15") (pinfunction "OUT4_15") (pintype "bidirectional"))
    )
    (net (code "64") (name "Net-(U$1-VREF12)") (class "Default")
      (node (ref "C14") (pin "1") (pinfunction "1_1") (pintype "passive"))
      (node (ref "R14") (pin "2") (pinfunction "2_2") (pintype "passive"))
      (node (ref "U$1") (pin "7") (pinfunction "VREF12_7") (pintype "bidirectional"))
    )
    (net (code "65") (name "Net-(U$1-VREF34)") (class "Default")
      (node (ref "C15") (pin "1") (pinfunction "1_1") (pintype "passive"))
      (node (ref "R15") (pin "2") (pinfunction "2_2") (pintype "passive"))
      (node (ref "U$1") (pin "2") (pinfunction "VREF34_2") (pintype "bidirectional"))
    )
    (net (code "66") (name "Net-(U$4-A)") (class "Default")
      (node (ref "JP10") (pin "6") (pinfunction "6_6") (pintype "passive"))
      (node (ref "U$4") (pin "6") (pinfunction "A_6") (pintype "bidirectional"))
    )
    (net (code "67") (name "Net-(U$4-B)") (class "Default")
      (node (ref "JP10") (pin "7") (pinfunction "7_7") (pintype "passive"))
      (node (ref "U$4") (pin "7") (pinfunction "B_7") (pintype "bidirectional"))
    )
    (net (code "68") (name "Net-(U$4-CLK)") (class "Default")
      (node (ref "JP10") (pin "2") (pinfunction "2_2") (pintype "passive"))
      (node (ref "U$4") (pin "2") (pinfunction "CLK_2") (pintype "bidirectional"))
    )
    (net (code "69") (name "Net-(U$4-CSN)") (class "Default")
      (node (ref "JP10") (pin "1") (pinfunction "1_1") (pintype "passive"))
      (node (ref "U$4") (pin "1") (pinfunction "CSN_1") (pintype "bidirectional"))
    )
    (net (code "70") (name "Net-(U$4-GND)") (class "Default")
      (node (ref "JP11") (pin "6") (pinfunction "6_6") (pintype "passive"))
      (node (ref "U$4") (pin "13") (pinfunction "GND_13") (pintype "bidirectional"))
    )
    (net (code "71") (name "Net-(U$4-I)") (class "Default")
      (node (ref "JP11") (pin "7") (pinfunction "7_7") (pintype "passive"))
      (node (ref "U$4") (pin "14") (pinfunction "I_14") (pintype "bidirectional"))
    )
    (net (code "72") (name "Net-(U$4-MISO)") (class "Default")
      (node (ref "JP10") (pin "3") (pinfunction "3_3") (pintype "passive"))
      (node (ref "U$4") (pin "3") (pinfunction "MISO_3") (pintype "bidirectional"))
    )
    (net (code "73") (name "Net-(U$4-MOSI)") (class "Default")
      (node (ref "JP10") (pin "4") (pinfunction "4_4") (pintype "passive"))
      (node (ref "U$4") (pin "4") (pinfunction "MOSI_4") (pintype "bidirectional"))
    )
    (net (code "74") (name "Net-(U$4-U)") (class "Default")
      (node (ref "JP11") (pin "3") (pinfunction "3_3") (pintype "passive"))
      (node (ref "U$4") (pin "10") (pinfunction "U_10") (pintype "bidirectional"))
    )
    (net (code "75") (name "Net-(U$4-V)") (class "Default")
      (node (ref "JP11") (pin "2") (pinfunction "2_2") (pintype "passive"))
      (node (ref "U$4") (pin "9") (pinfunction "V_9") (pintype "bidirectional"))
    )
    (net (code "76") (name "Net-(U$4-VDD)") (class "Default")
      (node (ref "C16") (pin "1") (pinfunction "1_1") (pintype "passive"))
      (node (ref "JP11") (pin "4") (pinfunction "4_4") (pintype "passive"))
      (node (ref "U$4") (pin "11") (pinfunction "VDD_11") (pintype "bidirectional"))
    )
    (net (code "77") (name "Net-(U$4-VDD3V)") (class "Default")
      (node (ref "C17") (pin "1") (pinfunction "1_1") (pintype "passive"))
      (node (ref "JP11") (pin "5") (pinfunction "5_5") (pintype "passive"))
      (node (ref "U$4") (pin "12") (pinfunction "VDD3V_12") (pintype "bidirectional"))
    )
    (net (code "78") (name "Net-(U$4-W)") (class "Default")
      (node (ref "JP11") (pin "1") (pinfunction "1_1") (pintype "passive"))
      (node (ref "U$4") (pin "8") (pinfunction "W_8") (pintype "bidirectional"))
    )
    (net (code "79") (name "PA03_AREFA") (class "Default")
      (node (ref "C4") (pin "1") (pinfunction "1_1") (pintype "passive"))
      (node (ref "IC1") (pin "4") (pinfunction "PA3/EIC/REF/AIN1_4") (pintype "bidirectional"))
      (node (ref "JP1") (pin "1") (pinfunction "1_1") (pintype "passive"))
    )
    (net (code "80") (name "SCK") (class "Default")
      (node (ref "IC1") (pin "26") (pinfunction "PA17/I2C/EIC/SCOM1PAD1+/TC2_26") (pintype "bidirectional"))
      (node (ref "JP2") (pin "7") (pinfunction "7_7") (pintype "passive"))
      (node (ref "Q2") (pin "1") (pinfunction "G_1") (pintype "passive"))
    )
    (net (code "81") (name "VBUS") (class "Default")
      (node (ref "C6") (pin "1") (pinfunction "1_1") (pintype "passive"))
      (node (ref "IC3") (pin "8") (pinfunction "IN1_8") (pintype "bidirectional"))
      (node (ref "IC4") (pin "1") (pinfunction "OUT_1") (pintype "power_in"))
      (node (ref "J1") (pin "1") (pinfunction "5V_1") (pintype "power_in"))
      (node (ref "JP2") (pin "12") (pinfunction "12_12") (pintype "passive"))
      (node (ref "R3") (pin "1") (pinfunction "1_1") (pintype "passive"))
    )
    (net (code "82") (name "VIN") (class "Default")
      (node (ref "IC3") (pin "6") (pinfunction "IN2_6") (pintype "bidirectional"))
      (node (ref "IC4") (pin "3") (pinfunction "IN_3") (pintype "power_in"))
      (node (ref "JP2") (pin "14") (pinfunction "14_14") (pintype "passive"))
    )
    (net (code "83") (name "VOUT") (class "Default")
      (node (ref "C9") (pin "1") (pinfunction "1_1") (pintype "passive"))
      (node (ref "IC2") (pin "1") (pinfunction "IN_1") (pintype "input"))
      (node (ref "IC2") (pin "3") (pinfunction "EN_3") (pintype "input"))
      (node (ref "IC3") (pin "7") (pinfunction "OUT_7") (pintype "bidirectional"))
      (node (ref "JP2") (pin "11") (pinfunction "11_11") (pintype "passive"))
      (node (ref "SJ1") (pin "1") (pinfunction "1_1") (pintype "passive"))
    )
    (net (code "84") (name "unconnected-(IC2-ADJ-Pad4)") (class "Default")
      (node (ref "IC2") (pin "4") (pinfunction "ADJ_4") (pintype "input"))
    )
    (net (code "85") (name "unconnected-(IC3-STAT-Pad1)") (class "Default")
      (node (ref "IC3") (pin "1") (pinfunction "STAT_1") (pintype "bidirectional"))
    )
    (net (code "86") (name "unconnected-(JP4-Pad6)") (class "Default")
      (node (ref "JP4") (pin "6") (pinfunction "6_6") (pintype "passive"))
    )
    (net (code "87") (name "unconnected-(JP4-Pad7)") (class "Default")
      (node (ref "JP4") (pin "7") (pinfunction "7_7") (pintype "passive"))
    )
    (net (code "88") (name "unconnected-(JP4-Pad8)") (class "Default")
      (node (ref "JP4") (pin "8") (pinfunction "8_8") (pintype "passive"))
    )
  )
)
